# ProPrj_AD8302__2025-07-18.net
KiCad netlist of a schematic drawn in EasyEDA Pro
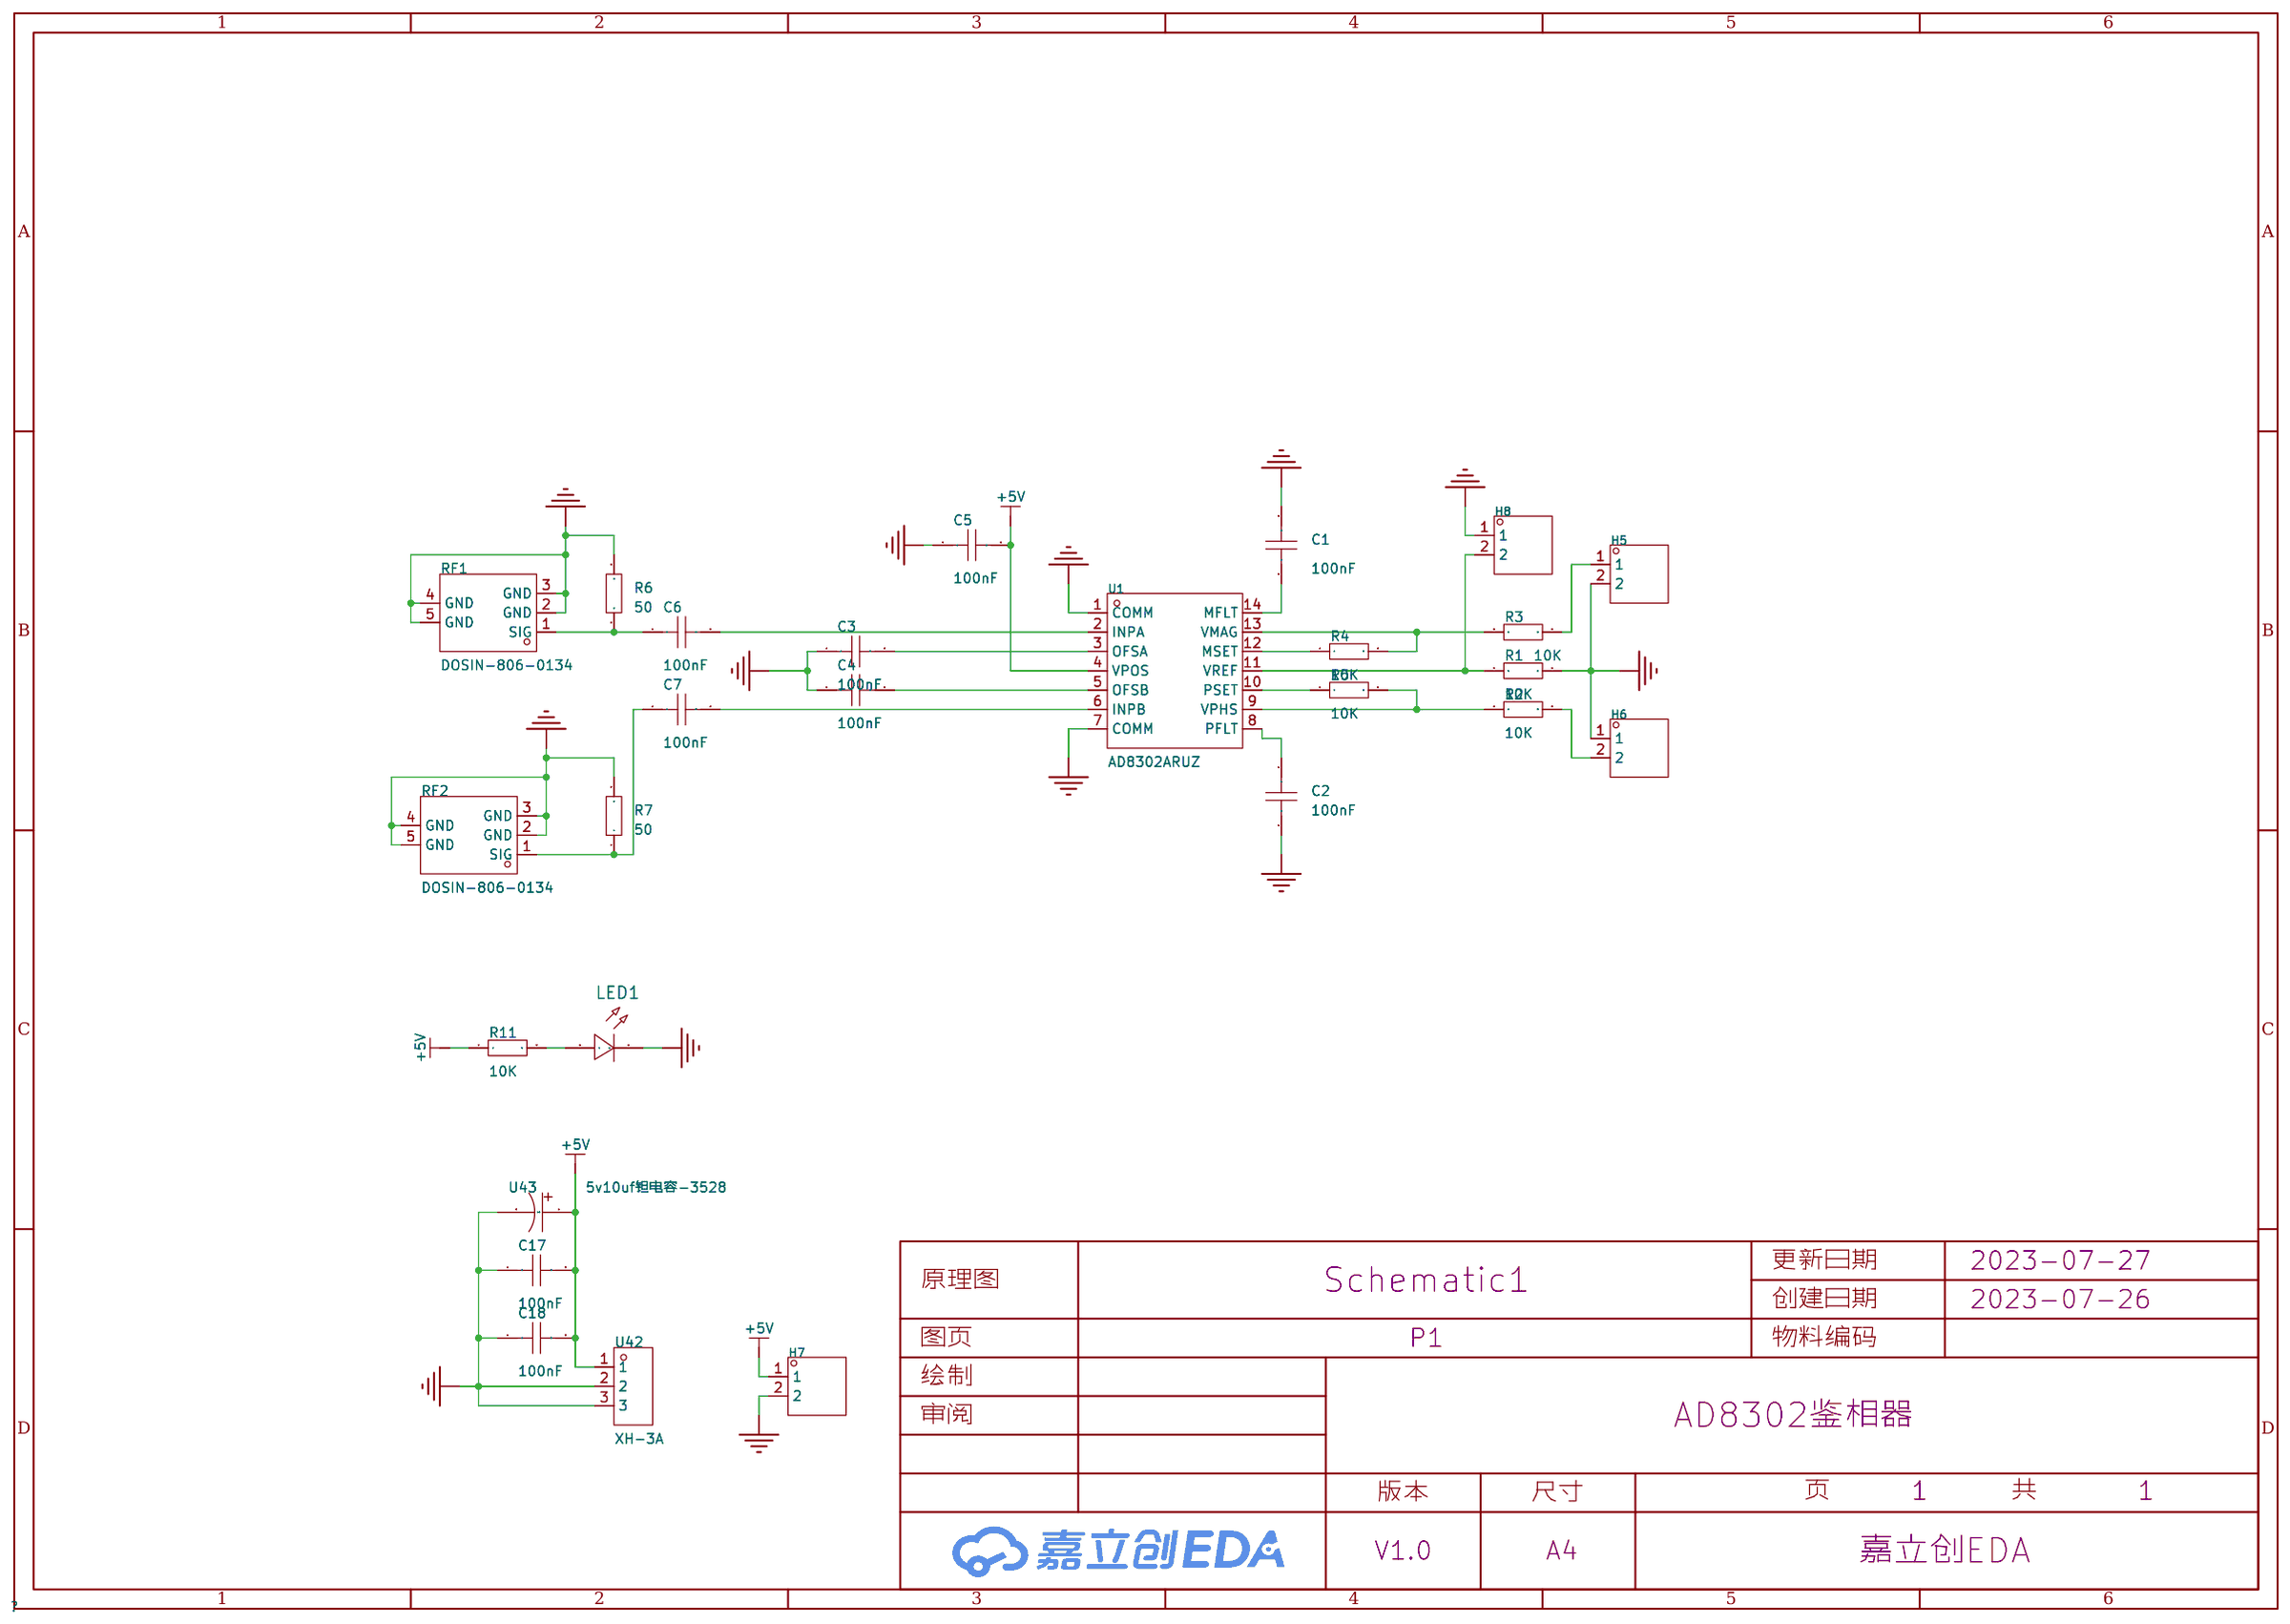
[diagram p0: schematic sheet]

(export (version "E")
  (design (tool "Eeschema 10.0.6"))
  (components
    (comp (ref "C1")
      (value "100nF")
      (footprint "easyedapro:C0603")
      (libsource (lib "easyedapro") (part "CapAcitance"))
    )
    (comp (ref "C2")
      (value "100nF")
      (footprint "easyedapro:C0603")
      (libsource (lib "easyedapro") (part "CapAcitance"))
    )
    (comp (ref "C3")
      (value "100nF")
      (footprint "easyedapro:C0603")
      (libsource (lib "easyedapro") (part "CapAcitance"))
    )
    (comp (ref "C4")
      (value "100nF")
      (footprint "easyedapro:C0603")
      (libsource (lib "easyedapro") (part "CapAcitance"))
    )
    (comp (ref "C5")
      (value "100nF")
      (footprint "easyedapro:C0603")
      (libsource (lib "easyedapro") (part "CapAcitance"))
    )
    (comp (ref "C6")
      (value "100nF")
      (footprint "easyedapro:C0603")
      (libsource (lib "easyedapro") (part "CapAcitance"))
    )
    (comp (ref "C7")
      (value "100nF")
      (footprint "easyedapro:C0603")
      (libsource (lib "easyedapro") (part "CapAcitance"))
    )
    (comp (ref "C17")
      (value "100nF")
      (footprint "easyedapro:C0603")
      (libsource (lib "easyedapro") (part "CapAcitance"))
    )
    (comp (ref "C18")
      (value "100nF")
      (footprint "easyedapro:C0603")
      (libsource (lib "easyedapro") (part "CapAcitance"))
    )
    (comp (ref "H5")
      (value "~")
      (footprint "easyedapro:HDR-TH_2P-P2.54-V-M-1")
      (libsource (lib "easyedapro") (part "210S-1*2P L=11.6MMGold-plated black"))
    )
    (comp (ref "H6")
      (value "~")
      (footprint "easyedapro:HDR-TH_2P-P2.54-V-M-1")
      (libsource (lib "easyedapro") (part "210S-1*2P L=11.6MMGold-plated black"))
    )
    (comp (ref "H7")
      (value "~")
      (footprint "easyedapro:HDR-TH_2P-P2.54-V-M-1")
      (libsource (lib "easyedapro") (part "210S-1*2P L=11.6MMGold-plated black"))
    )
    (comp (ref "H8")
      (value "~")
      (footprint "easyedapro:HDR-TH_2P-P2.54-V-M-1")
      (libsource (lib "easyedapro") (part "210S-1*2P L=11.6MMGold-plated black"))
    )
    (comp (ref "LED1")
      (value "~")
      (footprint "easyedapro:LED_0603")
      (libsource (lib "easyedapro") (part "LED_R"))
    )
    (comp (ref "R1") (value "10K") (footprint "easyedapro:R0603") (libsource (lib "easyedapro") (part "电阻")))
    (comp (ref "R2") (value "10K") (footprint "easyedapro:R0603") (libsource (lib "easyedapro") (part "电阻")))
    (comp (ref "R3") (value "10K") (footprint "easyedapro:R0603") (libsource (lib "easyedapro") (part "电阻")))
    (comp (ref "R4") (value "10K") (footprint "easyedapro:R0603") (libsource (lib "easyedapro") (part "电阻")))
    (comp (ref "R5") (value "10K") (footprint "easyedapro:R0603") (libsource (lib "easyedapro") (part "电阻")))
    (comp (ref "R6") (value "50") (footprint "easyedapro:R0603") (libsource (lib "easyedapro") (part "电阻")))
    (comp (ref "R7") (value "50") (footprint "easyedapro:R0603") (libsource (lib "easyedapro") (part "电阻")))
    (comp (ref "R11") (value "10K") (footprint "easyedapro:R0603") (libsource (lib "easyedapro") (part "电阻")))
    (comp (ref "RF1")
      (value "DOSIN-806-0134")
      (footprint "easyedapro:SMA-SMD_DOSIN-806-0134")
      (fields (field (name "Manufacturer") "dosinconn(德索五金)"))
      (libsource (lib "easyedapro") (part "DOSIN-806-0134"))
    )
    (comp (ref "RF2")
      (value "DOSIN-806-0134")
      (footprint "easyedapro:SMA-SMD_DOSIN-806-0134")
      (fields (field (name "Manufacturer") "dosinconn(德索五金)"))
      (libsource (lib "easyedapro") (part "DOSIN-806-0134"))
    )
    (comp (ref "U1")
      (value "AD8302ARUZ")
      (footprint "easyedapro:TSSOP-14_L5.0-W4.4-P0.65-LS6.4-BL")
      (description "应用领域:通用;频率范围:2.7GHz;输入范围:-60dBm~0dBm;精度:±0.5dB;")
      (fields (field (name "Manufacturer") "ADI(亚德诺)"))
      (libsource (lib "easyedapro") (part "AD8302ARUZ"))
    )
    (comp (ref "U42")
      (value "XH-3A")
      (footprint "easyedapro:CONN-TH_3P-P2.50_C9900023074")
      (libsource (lib "easyedapro") (part "XH-3A_C9900023074"))
    )
    (comp (ref "U43")
      (value "5v10uf钽电容-3528")
      (footprint "easyedapro:CAP-SMD_L3.5-W2.8")
      (libsource (lib "easyedapro") (part "5V10UF钽电容-3528"))
    )
  )
  (nets
    (net (code "1") (name "+5V") (class "Default")
      (node (ref "C17") (pin "2") (pinfunction "2_2") (pintype "input"))
      (node (ref "C18") (pin "2") (pinfunction "2_2") (pintype "input"))
      (node (ref "C5") (pin "2") (pinfunction "2_2") (pintype "input"))
      (node (ref "H7") (pin "1") (pinfunction "1_1") (pintype "input"))
      (node (ref "R11") (pin "1") (pinfunction "1_1") (pintype "input"))
      (node (ref "U1") (pin "4") (pinfunction "VPOS_4") (pintype "input"))
      (node (ref "U42") (pin "1") (pinfunction "1_1") (pintype "input"))
      (node (ref "U43") (pin "1") (pinfunction "1_1") (pintype "input"))
    )
    (net (code "2") (name "GND") (class "Default")
      (node (ref "C1") (pin "2") (pinfunction "2_2") (pintype "input"))
      (node (ref "C17") (pin "1") (pinfunction "1_1") (pintype "input"))
      (node (ref "C18") (pin "1") (pinfunction "1_1") (pintype "input"))
      (node (ref "C2") (pin "1") (pinfunction "1_1") (pintype "input"))
      (node (ref "C3") (pin "1") (pinfunction "1_1") (pintype "input"))
      (node (ref "C4") (pin "1") (pinfunction "1_1") (pintype "input"))
      (node (ref "C5") (pin "1") (pinfunction "1_1") (pintype "input"))
      (node (ref "H5") (pin "2") (pinfunction "2_2") (pintype "input"))
      (node (ref "H6") (pin "1") (pinfunction "1_1") (pintype "input"))
      (node (ref "H7") (pin "2") (pinfunction "2_2") (pintype "input"))
      (node (ref "H8") (pin "1") (pinfunction "1_1") (pintype "input"))
      (node (ref "LED1") (pin "1") (pinfunction "C_1") (pintype "input"))
      (node (ref "R1") (pin "2") (pinfunction "2_2") (pintype "input"))
      (node (ref "R6") (pin "2") (pinfunction "2_2") (pintype "input"))
      (node (ref "R7") (pin "2") (pinfunction "2_2") (pintype "input"))
      (node (ref "RF1") (pin "2") (pinfunction "GND_2") (pintype "input"))
      (node (ref "RF1") (pin "3") (pinfunction "GND_3") (pintype "input"))
      (node (ref "RF1") (pin "4") (pinfunction "GND_4") (pintype "input"))
      (node (ref "RF1") (pin "5") (pinfunction "GND_5") (pintype "input"))
      (node (ref "RF2") (pin "2") (pinfunction "GND_2") (pintype "input"))
      (node (ref "RF2") (pin "3") (pinfunction "GND_3") (pintype "input"))
      (node (ref "RF2") (pin "4") (pinfunction "GND_4") (pintype "input"))
      (node (ref "RF2") (pin "5") (pinfunction "GND_5") (pintype "input"))
      (node (ref "U1") (pin "1") (pinfunction "COMM_1") (pintype "input"))
      (node (ref "U1") (pin "7") (pinfunction "COMM_7") (pintype "input"))
      (node (ref "U42") (pin "2") (pinfunction "2_2") (pintype "input"))
      (node (ref "U42") (pin "3") (pinfunction "3_3") (pintype "input"))
      (node (ref "U43") (pin "2") (pinfunction "2_2") (pintype "input"))
    )
    (net (code "3") (name "Net-(H5-Pad1)") (class "Default")
      (node (ref "H5") (pin "1") (pinfunction "1_1") (pintype "input"))
      (node (ref "R3") (pin "2") (pinfunction "2_2") (pintype "input"))
    )
    (net (code "4") (name "Net-(H6-Pad2)") (class "Default")
      (node (ref "H6") (pin "2") (pinfunction "2_2") (pintype "input"))
      (node (ref "R2") (pin "2") (pinfunction "2_2") (pintype "input"))
    )
    (net (code "5") (name "Net-(LED1-A)") (class "Default")
      (node (ref "LED1") (pin "2") (pinfunction "A_2") (pintype "input"))
      (node (ref "R11") (pin "2") (pinfunction "2_2") (pintype "input"))
    )
    (net (code "6") (name "Net-(RF1-SIG)") (class "Default")
      (node (ref "C6") (pin "1") (pinfunction "1_1") (pintype "input"))
      (node (ref "R6") (pin "1") (pinfunction "1_1") (pintype "input"))
      (node (ref "RF1") (pin "1") (pinfunction "SIG_1") (pintype "input"))
    )
    (net (code "7") (name "Net-(RF2-SIG)") (class "Default")
      (node (ref "C7") (pin "1") (pinfunction "1_1") (pintype "input"))
      (node (ref "R7") (pin "1") (pinfunction "1_1") (pintype "input"))
      (node (ref "RF2") (pin "1") (pinfunction "SIG_1") (pintype "input"))
    )
    (net (code "8") (name "Net-(U1-INPA)") (class "Default")
      (node (ref "C6") (pin "2") (pinfunction "2_2") (pintype "input"))
      (node (ref "U1") (pin "2") (pinfunction "INPA_2") (pintype "input"))
    )
    (net (code "9") (name "Net-(U1-INPB)") (class "Default")
      (node (ref "C7") (pin "2") (pinfunction "2_2") (pintype "input"))
      (node (ref "U1") (pin "6") (pinfunction "INPB_6") (pintype "input"))
    )
    (net (code "10") (name "Net-(U1-MFLT)") (class "Default")
      (node (ref "C1") (pin "1") (pinfunction "1_1") (pintype "input"))
      (node (ref "U1") (pin "14") (pinfunction "MFLT_14") (pintype "input"))
    )
    (net (code "11") (name "Net-(U1-MSET)") (class "Default")
      (node (ref "R4") (pin "1") (pinfunction "1_1") (pintype "input"))
      (node (ref "U1") (pin "12") (pinfunction "MSET_12") (pintype "input"))
    )
    (net (code "12") (name "Net-(U1-OFSA)") (class "Default")
      (node (ref "C3") (pin "2") (pinfunction "2_2") (pintype "input"))
      (node (ref "U1") (pin "3") (pinfunction "OFSA_3") (pintype "input"))
    )
    (net (code "13") (name "Net-(U1-OFSB)") (class "Default")
      (node (ref "C4") (pin "2") (pinfunction "2_2") (pintype "input"))
      (node (ref "U1") (pin "5") (pinfunction "OFSB_5") (pintype "input"))
    )
    (net (code "14") (name "Net-(U1-PFLT)") (class "Default")
      (node (ref "C2") (pin "2") (pinfunction "2_2") (pintype "input"))
      (node (ref "U1") (pin "8") (pinfunction "PFLT_8") (pintype "input"))
    )
    (net (code "15") (name "Net-(U1-PSET)") (class "Default")
      (node (ref "R5") (pin "1") (pinfunction "1_1") (pintype "input"))
      (node (ref "U1") (pin "10") (pinfunction "PSET_10") (pintype "input"))
    )
    (net (code "16") (name "Net-(U1-VMAG)") (class "Default")
      (node (ref "R3") (pin "1") (pinfunction "1_1") (pintype "input"))
      (node (ref "R4") (pin "2") (pinfunction "2_2") (pintype "input"))
      (node (ref "U1") (pin "13") (pinfunction "VMAG_13") (pintype "input"))
    )
    (net (code "17") (name "Net-(U1-VPHS)") (class "Default")
      (node (ref "R2") (pin "1") (pinfunction "1_1") (pintype "input"))
      (node (ref "R5") (pin "2") (pinfunction "2_2") (pintype "input"))
      (node (ref "U1") (pin "9") (pinfunction "VPHS_9") (pintype "input"))
    )
    (net (code "18") (name "Net-(U1-VREF)") (class "Default")
      (node (ref "H8") (pin "2") (pinfunction "2_2") (pintype "input"))
      (node (ref "R1") (pin "1") (pinfunction "1_1") (pintype "input"))
      (node (ref "U1") (pin "11") (pinfunction "VREF_11") (pintype "input"))
    )
  )
)
